# tinyusbboard.net
KiCad netlist of a schematic drawn in EAGLE
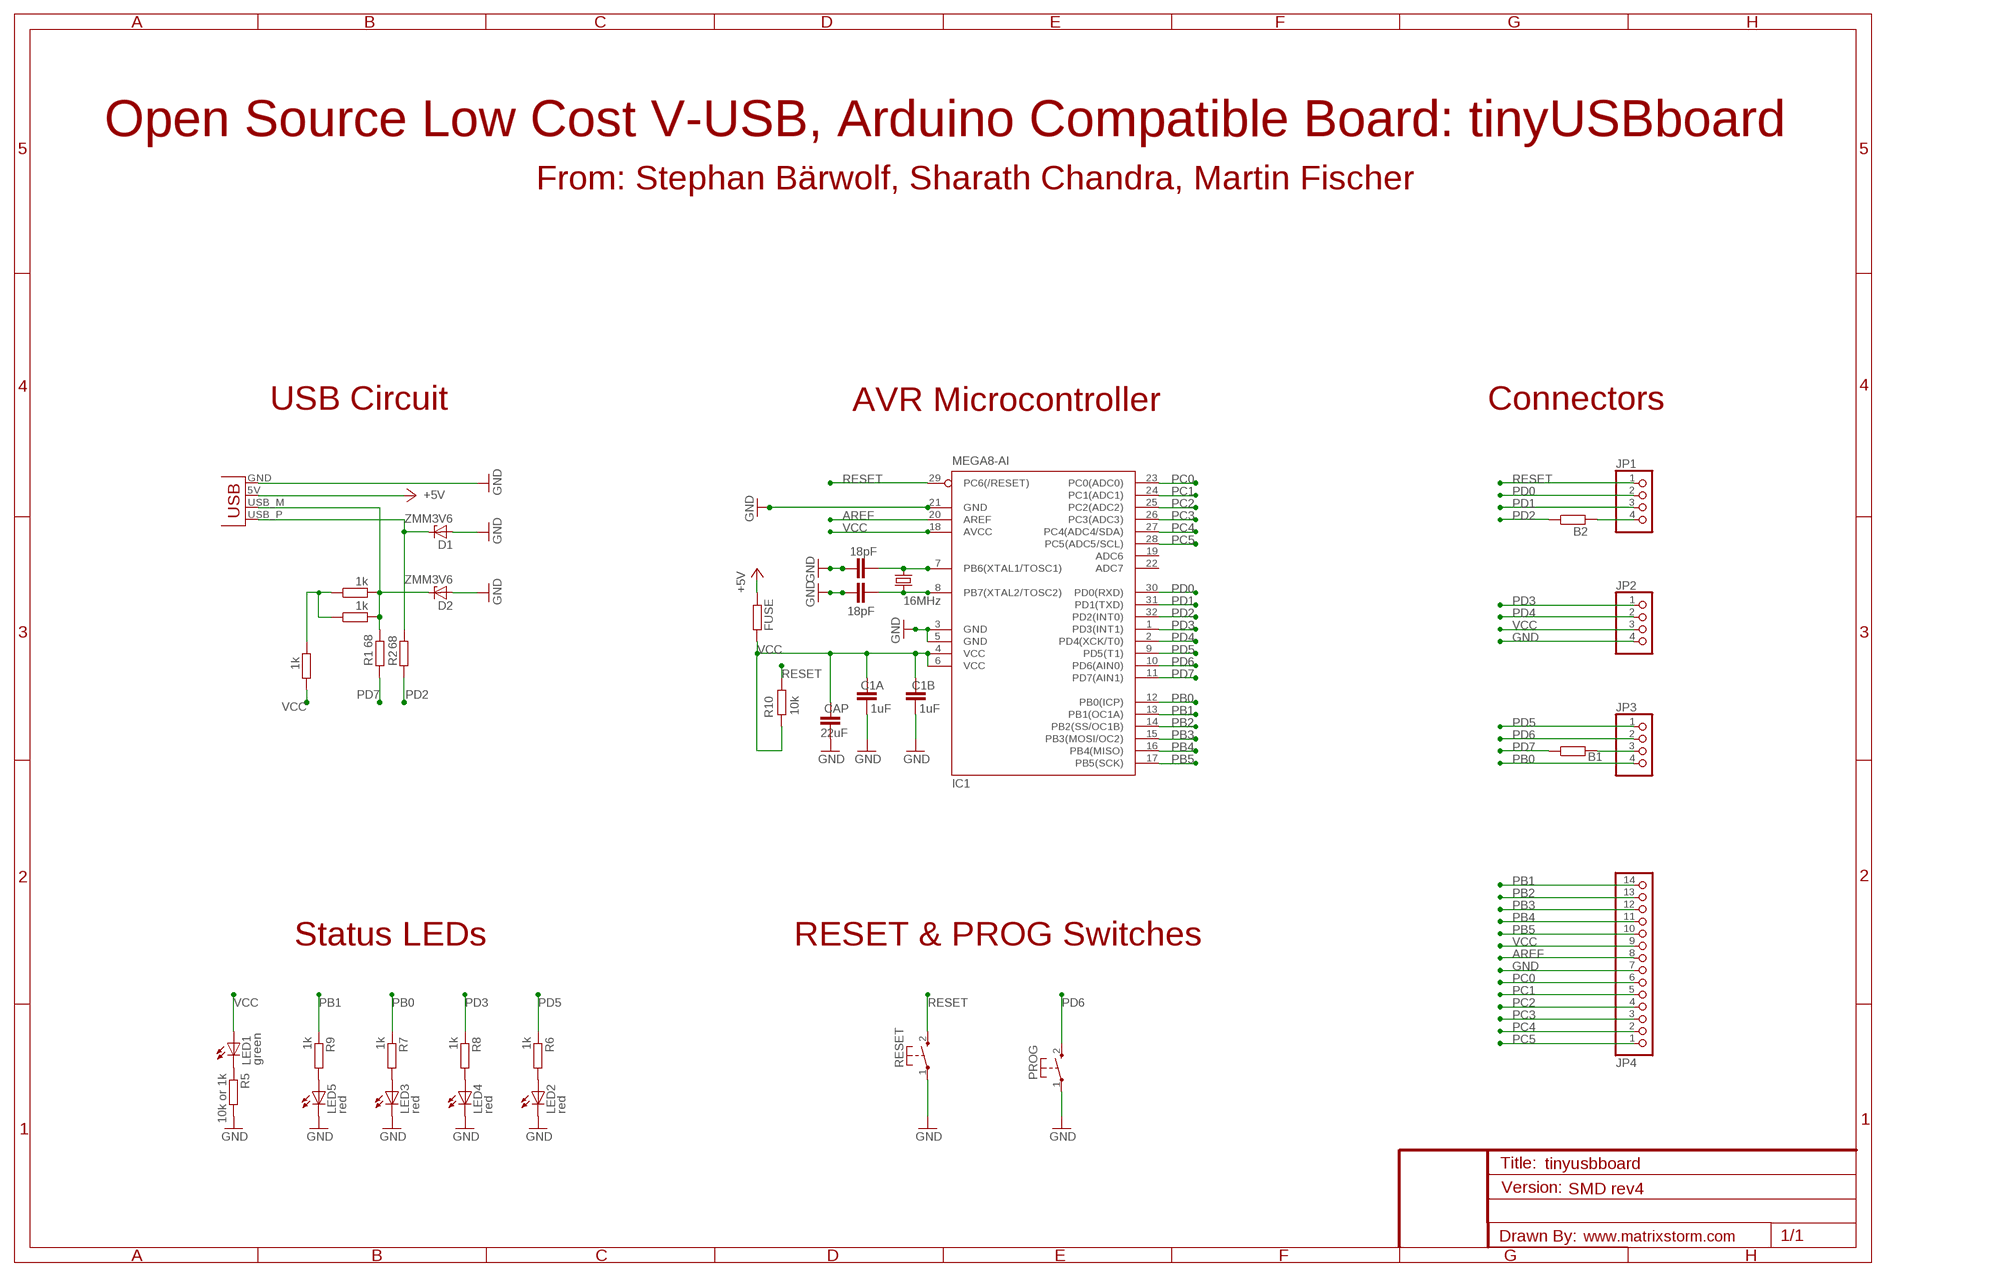
[diagram p0: schematic, sheet 1]

(export (version "E")
  (design (tool "Eeschema 10.0.6"))
  (components
    (comp (ref "AQ1")
      (value "16MHz")
      (footprint "eagle-import:CRYSTAL-SMD-5X3")
      (libsource (lib "eagle-import") (part "CRYSTAL5X3"))
    )
    (comp (ref "B1")
      (value "0")
      (footprint "eagle-import:R0805W")
      (libsource (lib "eagle-import") (part "R-EU_R0805W"))
    )
    (comp (ref "B2")
      (value "0")
      (footprint "eagle-import:R0805W")
      (libsource (lib "eagle-import") (part "R-EU_R0805W"))
    )
    (comp (ref "C1A")
      (value "1uF")
      (footprint "eagle-import:C0805K")
      (libsource (lib "eagle-import") (part "C-EUC0805K"))
    )
    (comp (ref "C1B")
      (value "1uF")
      (footprint "eagle-import:C0805K")
      (libsource (lib "eagle-import") (part "C-EUC0805K"))
    )
    (comp (ref "C2")
      (value "18pF")
      (footprint "eagle-import:C0805K")
      (libsource (lib "eagle-import") (part "C-EUC0805K"))
    )
    (comp (ref "C3")
      (value "18pF")
      (footprint "eagle-import:C0805K")
      (libsource (lib "eagle-import") (part "C-EUC0805K"))
    )
    (comp (ref "CAP")
      (value "22uF")
      (footprint "eagle-import:C1206K")
      (libsource (lib "eagle-import") (part "C-EUC1206K"))
    )
    (comp (ref "D1")
      (value "ZMM3V6")
      (footprint "eagle-import:SOD80")
      (libsource (lib "eagle-import") (part "ZD-SOD-80"))
    )
    (comp (ref "D2")
      (value "ZMM3V6")
      (footprint "eagle-import:SOD80")
      (libsource (lib "eagle-import") (part "ZD-SOD-80"))
    )
    (comp (ref "FUSE")
      (value "0")
      (footprint "eagle-import:R1206W")
      (libsource (lib "eagle-import") (part "R-EU_R1206W"))
    )
    (comp (ref "IC1")
      (value "MEGA8-AI")
      (footprint "eagle-import:TQFP32-08")
      (fields (field (name "MPN") "ATMEGA8-16AU"))
      (libsource (lib "eagle-import") (part "MEGA8-AI"))
    )
    (comp (ref "JP1")
      (value "PINHD-1X4")
      (footprint "eagle-import:1X04")
      (libsource (lib "eagle-import") (part "PINHD-1X4"))
    )
    (comp (ref "JP2")
      (value "PINHD-1X4")
      (footprint "eagle-import:1X04")
      (libsource (lib "eagle-import") (part "PINHD-1X4"))
    )
    (comp (ref "JP3")
      (value "PINHD-1X4")
      (footprint "eagle-import:1X04")
      (libsource (lib "eagle-import") (part "PINHD-1X4"))
    )
    (comp (ref "JP4")
      (value "PINHD-1X14")
      (footprint "eagle-import:1X14")
      (libsource (lib "eagle-import") (part "PINHD-1X14"))
    )
    (comp (ref "LED1")
      (value "green")
      (footprint "eagle-import:CHIPLED_0805")
      (libsource (lib "eagle-import") (part "LEDCHIPLED_0805"))
    )
    (comp (ref "LED2")
      (value "red")
      (footprint "eagle-import:CHIPLED_0805")
      (libsource (lib "eagle-import") (part "LEDCHIPLED_0805"))
    )
    (comp (ref "LED3")
      (value "red")
      (footprint "eagle-import:CHIPLED_0805")
      (libsource (lib "eagle-import") (part "LEDCHIPLED_0805"))
    )
    (comp (ref "LED4")
      (value "red")
      (footprint "eagle-import:CHIPLED_0805")
      (libsource (lib "eagle-import") (part "LEDCHIPLED_0805"))
    )
    (comp (ref "LED5")
      (value "red")
      (footprint "eagle-import:CHIPLED_0805")
      (libsource (lib "eagle-import") (part "LEDCHIPLED_0805"))
    )
    (comp (ref "PROG")
      (value "KSS-2EG4430")
      (footprint "eagle-import:KSS-2EG4430")
      (libsource (lib "eagle-import") (part "KSS-2EG4430"))
    )
    (comp (ref "Q1")
      (value "16MHz")
      (footprint "eagle-import:HC49_S")
      (libsource (lib "eagle-import") (part "CRYSTALHC49S"))
    )
    (comp (ref "R1")
      (value "68")
      (footprint "eagle-import:R0805W")
      (libsource (lib "eagle-import") (part "R-EU_R0805W"))
    )
    (comp (ref "R2")
      (value "68")
      (footprint "eagle-import:R0805W")
      (libsource (lib "eagle-import") (part "R-EU_R0805W"))
    )
    (comp (ref "R3")
      (value "1k")
      (footprint "eagle-import:R0805W")
      (libsource (lib "eagle-import") (part "R-EU_R0805W"))
    )
    (comp (ref "R3A")
      (value "1k")
      (footprint "eagle-import:R0805W")
      (libsource (lib "eagle-import") (part "R-EU_R0805W"))
    )
    (comp (ref "R3B")
      (value "1k")
      (footprint "eagle-import:R0805W")
      (libsource (lib "eagle-import") (part "R-EU_R0805W"))
    )
    (comp (ref "R5")
      (value "10k or 1k")
      (footprint "eagle-import:R0805W")
      (libsource (lib "eagle-import") (part "R-EU_R0805W"))
    )
    (comp (ref "R6")
      (value "1k")
      (footprint "eagle-import:R0805W")
      (libsource (lib "eagle-import") (part "R-EU_R0805W"))
    )
    (comp (ref "R7")
      (value "1k")
      (footprint "eagle-import:R0805W")
      (libsource (lib "eagle-import") (part "R-EU_R0805W"))
    )
    (comp (ref "R8")
      (value "1k")
      (footprint "eagle-import:R0805W")
      (libsource (lib "eagle-import") (part "R-EU_R0805W"))
    )
    (comp (ref "R9")
      (value "1k")
      (footprint "eagle-import:R0805W")
      (libsource (lib "eagle-import") (part "R-EU_R0805W"))
    )
    (comp (ref "R10")
      (value "10k")
      (footprint "eagle-import:R0805W")
      (libsource (lib "eagle-import") (part "R-EU_R0805W"))
    )
    (comp (ref "RESET")
      (value "KSS-2EG4430")
      (footprint "eagle-import:KSS-2EG4430")
      (libsource (lib "eagle-import") (part "KSS-2EG4430"))
    )
    (comp (ref "USB")
      (value "USBPCB")
      (footprint "eagle-import:USB-A-PCB")
      (libsource (lib "eagle-import") (part "USBPCB"))
    )
  )
  (nets
    (net (code "1") (name "+5V") (class "Default")
      (node (ref "FUSE") (pin "1") (pinfunction "1_1") (pintype "passive"))
      (node (ref "USB") (pin "5V") (pinfunction "VBUS_5V") (pintype "bidirectional"))
    )
    (net (code "2") (name "/AREF") (class "Default")
      (node (ref "IC1") (pin "20") (pinfunction "AREF_20") (pintype "passive"))
      (node (ref "JP4") (pin "8") (pinfunction "8_8") (pintype "passive"))
    )
    (net (code "3") (name "/PB0") (class "Default")
      (node (ref "IC1") (pin "12") (pinfunction "PB0(ICP)_12") (pintype "bidirectional"))
      (node (ref "JP3") (pin "4") (pinfunction "4_4") (pintype "passive"))
      (node (ref "R7") (pin "1") (pinfunction "1_1") (pintype "passive"))
    )
    (net (code "4") (name "/PB1") (class "Default")
      (node (ref "IC1") (pin "13") (pinfunction "PB1(OC1A)_13") (pintype "bidirectional"))
      (node (ref "JP4") (pin "14") (pinfunction "14_14") (pintype "passive"))
      (node (ref "R9") (pin "1") (pinfunction "1_1") (pintype "passive"))
    )
    (net (code "5") (name "/PB2") (class "Default")
      (node (ref "IC1") (pin "14") (pinfunction "PB2(SS/OC1B)_14") (pintype "bidirectional"))
      (node (ref "JP4") (pin "13") (pinfunction "13_13") (pintype "passive"))
    )
    (net (code "6") (name "/PB3") (class "Default")
      (node (ref "IC1") (pin "15") (pinfunction "PB3(MOSI/OC2)_15") (pintype "bidirectional"))
      (node (ref "JP4") (pin "12") (pinfunction "12_12") (pintype "passive"))
    )
    (net (code "7") (name "/PB4") (class "Default")
      (node (ref "IC1") (pin "16") (pinfunction "PB4(MISO)_16") (pintype "bidirectional"))
      (node (ref "JP4") (pin "11") (pinfunction "11_11") (pintype "passive"))
    )
    (net (code "8") (name "/PB5") (class "Default")
      (node (ref "IC1") (pin "17") (pinfunction "PB5(SCK)_17") (pintype "bidirectional"))
      (node (ref "JP4") (pin "10") (pinfunction "10_10") (pintype "passive"))
    )
    (net (code "9") (name "/PC0") (class "Default")
      (node (ref "IC1") (pin "23") (pinfunction "PC0(ADC0)_23") (pintype "bidirectional"))
      (node (ref "JP4") (pin "6") (pinfunction "6_6") (pintype "passive"))
    )
    (net (code "10") (name "/PC1") (class "Default")
      (node (ref "IC1") (pin "24") (pinfunction "PC1(ADC1)_24") (pintype "bidirectional"))
      (node (ref "JP4") (pin "5") (pinfunction "5_5") (pintype "passive"))
    )
    (net (code "11") (name "/PC2") (class "Default")
      (node (ref "IC1") (pin "25") (pinfunction "PC2(ADC2)_25") (pintype "bidirectional"))
      (node (ref "JP4") (pin "4") (pinfunction "4_4") (pintype "passive"))
    )
    (net (code "12") (name "/PC3") (class "Default")
      (node (ref "IC1") (pin "26") (pinfunction "PC3(ADC3)_26") (pintype "bidirectional"))
      (node (ref "JP4") (pin "3") (pinfunction "3_3") (pintype "passive"))
    )
    (net (code "13") (name "/PC4") (class "Default")
      (node (ref "IC1") (pin "27") (pinfunction "PC4(ADC4/SDA)_27") (pintype "bidirectional"))
      (node (ref "JP4") (pin "2") (pinfunction "2_2") (pintype "passive"))
    )
    (net (code "14") (name "/PC5") (class "Default")
      (node (ref "IC1") (pin "28") (pinfunction "PC5(ADC5/SCL)_28") (pintype "bidirectional"))
      (node (ref "JP4") (pin "1") (pinfunction "1_1") (pintype "passive"))
    )
    (net (code "15") (name "/PD0") (class "Default")
      (node (ref "IC1") (pin "30") (pinfunction "PD0(RXD)_30") (pintype "bidirectional"))
      (node (ref "JP1") (pin "2") (pinfunction "2_2") (pintype "passive"))
    )
    (net (code "16") (name "/PD1") (class "Default")
      (node (ref "IC1") (pin "31") (pinfunction "PD1(TXD)_31") (pintype "bidirectional"))
      (node (ref "JP1") (pin "3") (pinfunction "3_3") (pintype "passive"))
    )
    (net (code "17") (name "/PD2") (class "Default")
      (node (ref "B2") (pin "1") (pinfunction "1_1") (pintype "passive"))
      (node (ref "IC1") (pin "32") (pinfunction "PD2(INT0)_32") (pintype "bidirectional"))
      (node (ref "R2") (pin "1") (pinfunction "1_1") (pintype "passive"))
    )
    (net (code "18") (name "/PD3") (class "Default")
      (node (ref "IC1") (pin "1") (pinfunction "PD3(INT1)_1") (pintype "bidirectional"))
      (node (ref "JP2") (pin "1") (pinfunction "1_1") (pintype "passive"))
      (node (ref "R8") (pin "1") (pinfunction "1_1") (pintype "passive"))
    )
    (net (code "19") (name "/PD4") (class "Default")
      (node (ref "IC1") (pin "2") (pinfunction "PD4(XCK/T0)_2") (pintype "bidirectional"))
      (node (ref "JP2") (pin "2") (pinfunction "2_2") (pintype "passive"))
    )
    (net (code "20") (name "/PD5") (class "Default")
      (node (ref "IC1") (pin "9") (pinfunction "PD5(T1)_9") (pintype "bidirectional"))
      (node (ref "JP3") (pin "1") (pinfunction "1_1") (pintype "passive"))
      (node (ref "R6") (pin "1") (pinfunction "1_1") (pintype "passive"))
    )
    (net (code "21") (name "/PD6") (class "Default")
      (node (ref "IC1") (pin "10") (pinfunction "PD6(AIN0)_10") (pintype "bidirectional"))
      (node (ref "JP3") (pin "2") (pinfunction "2_2") (pintype "passive"))
      (node (ref "PROG") (pin "2") (pinfunction "S_2") (pintype "passive"))
    )
    (net (code "22") (name "/PD7") (class "Default")
      (node (ref "B1") (pin "1") (pinfunction "1_1") (pintype "passive"))
      (node (ref "IC1") (pin "11") (pinfunction "PD7(AIN1)_11") (pintype "bidirectional"))
      (node (ref "R1") (pin "1") (pinfunction "1_1") (pintype "passive"))
    )
    (net (code "23") (name "/RESET") (class "Default")
      (node (ref "IC1") (pin "29") (pinfunction "PC6(/RESET)_29") (pintype "bidirectional"))
      (node (ref "JP1") (pin "1") (pinfunction "1_1") (pintype "passive"))
      (node (ref "R10") (pin "1") (pinfunction "1_1") (pintype "passive"))
      (node (ref "RESET") (pin "2") (pinfunction "S_2") (pintype "passive"))
    )
    (net (code "24") (name "/VCC") (class "Default")
      (node (ref "C1A") (pin "1") (pinfunction "1_1") (pintype "passive"))
      (node (ref "C1B") (pin "1") (pinfunction "1_1") (pintype "passive"))
      (node (ref "CAP") (pin "1") (pinfunction "1_1") (pintype "passive"))
      (node (ref "FUSE") (pin "2") (pinfunction "2_2") (pintype "passive"))
      (node (ref "IC1") (pin "18") (pinfunction "AVCC_18") (pintype "power_in"))
      (node (ref "IC1") (pin "4") (pinfunction "VCC_4") (pintype "power_in"))
      (node (ref "IC1") (pin "6") (pinfunction "VCC_6") (pintype "power_in"))
      (node (ref "JP2") (pin "3") (pinfunction "3_3") (pintype "passive"))
      (node (ref "JP4") (pin "9") (pinfunction "9_9") (pintype "passive"))
      (node (ref "LED1") (pin "A") (pinfunction "A_A") (pintype "passive"))
      (node (ref "R10") (pin "2") (pinfunction "2_2") (pintype "passive"))
      (node (ref "R3") (pin "2") (pinfunction "2_2") (pintype "passive"))
    )
    (net (code "25") (name "GND") (class "Default")
      (node (ref "C1A") (pin "2") (pinfunction "2_2") (pintype "passive"))
      (node (ref "C1B") (pin "2") (pinfunction "2_2") (pintype "passive"))
      (node (ref "C2") (pin "2") (pinfunction "2_2") (pintype "passive"))
      (node (ref "C3") (pin "2") (pinfunction "2_2") (pintype "passive"))
      (node (ref "CAP") (pin "2") (pinfunction "2_2") (pintype "passive"))
      (node (ref "D1") (pin "A") (pinfunction "A_A") (pintype "passive"))
      (node (ref "D2") (pin "A") (pinfunction "A_A") (pintype "passive"))
      (node (ref "IC1") (pin "21") (pinfunction "GND_21") (pintype "power_in"))
      (node (ref "IC1") (pin "3") (pinfunction "GND_3") (pintype "power_in"))
      (node (ref "IC1") (pin "5") (pinfunction "GND_5") (pintype "power_in"))
      (node (ref "JP2") (pin "4") (pinfunction "4_4") (pintype "passive"))
      (node (ref "JP4") (pin "7") (pinfunction "7_7") (pintype "passive"))
      (node (ref "LED2") (pin "C") (pinfunction "C_C") (pintype "passive"))
      (node (ref "LED3") (pin "C") (pinfunction "C_C") (pintype "passive"))
      (node (ref "LED4") (pin "C") (pinfunction "C_C") (pintype "passive"))
      (node (ref "LED5") (pin "C") (pinfunction "C_C") (pintype "passive"))
      (node (ref "PROG") (pin "1") (pinfunction "P_1") (pintype "passive"))
      (node (ref "R5") (pin "2") (pinfunction "2_2") (pintype "passive"))
      (node (ref "RESET") (pin "1") (pinfunction "P_1") (pintype "passive"))
      (node (ref "USB") (pin "GND") (pinfunction "GND_GND") (pintype "bidirectional"))
    )
    (net (code "26") (name "Net-(AQ1-2)") (class "Default")
      (node (ref "AQ1") (pin "3") (pinfunction "2_3") (pintype "passive"))
      (node (ref "C2") (pin "1") (pinfunction "1_1") (pintype "passive"))
      (node (ref "IC1") (pin "8") (pinfunction "PB7(XTAL2/TOSC2)_8") (pintype "bidirectional"))
      (node (ref "Q1") (pin "2") (pinfunction "2_2") (pintype "passive"))
    )
    (net (code "27") (name "Net-(B1-Pad2)") (class "Default")
      (node (ref "B1") (pin "2") (pinfunction "2_2") (pintype "passive"))
      (node (ref "JP3") (pin "3") (pinfunction "3_3") (pintype "passive"))
    )
    (net (code "28") (name "Net-(B2-Pad2)") (class "Default")
      (node (ref "B2") (pin "2") (pinfunction "2_2") (pintype "passive"))
      (node (ref "JP1") (pin "4") (pinfunction "4_4") (pintype "passive"))
    )
    (net (code "29") (name "Net-(IC1-PB6(XTAL1{slash}TOSC1))") (class "Default")
      (node (ref "AQ1") (pin "1") (pinfunction "1_1") (pintype "passive"))
      (node (ref "C3") (pin "1") (pinfunction "1_1") (pintype "passive"))
      (node (ref "IC1") (pin "7") (pinfunction "PB6(XTAL1/TOSC1)_7") (pintype "bidirectional"))
      (node (ref "Q1") (pin "1") (pinfunction "1_1") (pintype "passive"))
    )
    (net (code "30") (name "Net-(LED1-PadC)") (class "Default")
      (node (ref "LED1") (pin "C") (pinfunction "C_C") (pintype "passive"))
      (node (ref "R5") (pin "1") (pinfunction "1_1") (pintype "passive"))
    )
    (net (code "31") (name "Net-(LED2-PadA)") (class "Default")
      (node (ref "LED2") (pin "A") (pinfunction "A_A") (pintype "passive"))
      (node (ref "R6") (pin "2") (pinfunction "2_2") (pintype "passive"))
    )
    (net (code "32") (name "Net-(LED3-PadA)") (class "Default")
      (node (ref "LED3") (pin "A") (pinfunction "A_A") (pintype "passive"))
      (node (ref "R7") (pin "2") (pinfunction "2_2") (pintype "passive"))
    )
    (net (code "33") (name "Net-(LED4-PadA)") (class "Default")
      (node (ref "LED4") (pin "A") (pinfunction "A_A") (pintype "passive"))
      (node (ref "R8") (pin "2") (pinfunction "2_2") (pintype "passive"))
    )
    (net (code "34") (name "Net-(LED5-PadA)") (class "Default")
      (node (ref "LED5") (pin "A") (pinfunction "A_A") (pintype "passive"))
      (node (ref "R9") (pin "2") (pinfunction "2_2") (pintype "passive"))
    )
    (net (code "35") (name "Net-(R3-Pad1)") (class "Default")
      (node (ref "R3") (pin "1") (pinfunction "1_1") (pintype "passive"))
      (node (ref "R3A") (pin "1") (pinfunction "1_1") (pintype "passive"))
      (node (ref "R3B") (pin "1") (pinfunction "1_1") (pintype "passive"))
    )
    (net (code "36") (name "Net-(USB-D+)") (class "Default")
      (node (ref "D1") (pin "C") (pinfunction "C_C") (pintype "passive"))
      (node (ref "R2") (pin "2") (pinfunction "2_2") (pintype "passive"))
      (node (ref "USB") (pin "USB_P") (pinfunction "D+_USB_P") (pintype "bidirectional"))
    )
    (net (code "37") (name "Net-(USB-D-)") (class "Default")
      (node (ref "D2") (pin "C") (pinfunction "C_C") (pintype "passive"))
      (node (ref "R1") (pin "2") (pinfunction "2_2") (pintype "passive"))
      (node (ref "R3A") (pin "2") (pinfunction "2_2") (pintype "passive"))
      (node (ref "R3B") (pin "2") (pinfunction "2_2") (pintype "passive"))
      (node (ref "USB") (pin "USB_M") (pinfunction "D-_USB_M") (pintype "bidirectional"))
    )
    (net (code "38") (name "unconnected-(IC1-ADC6-Pad19)") (class "Default")
      (node (ref "IC1") (pin "19") (pinfunction "ADC6_19") (pintype "bidirectional"))
    )
    (net (code "39") (name "unconnected-(IC1-ADC7-Pad22)") (class "Default")
      (node (ref "IC1") (pin "22") (pinfunction "ADC7_22") (pintype "bidirectional"))
    )
  )
)
